# 7SEG-3.net
KiCad netlist of a schematic drawn in Altium Designer
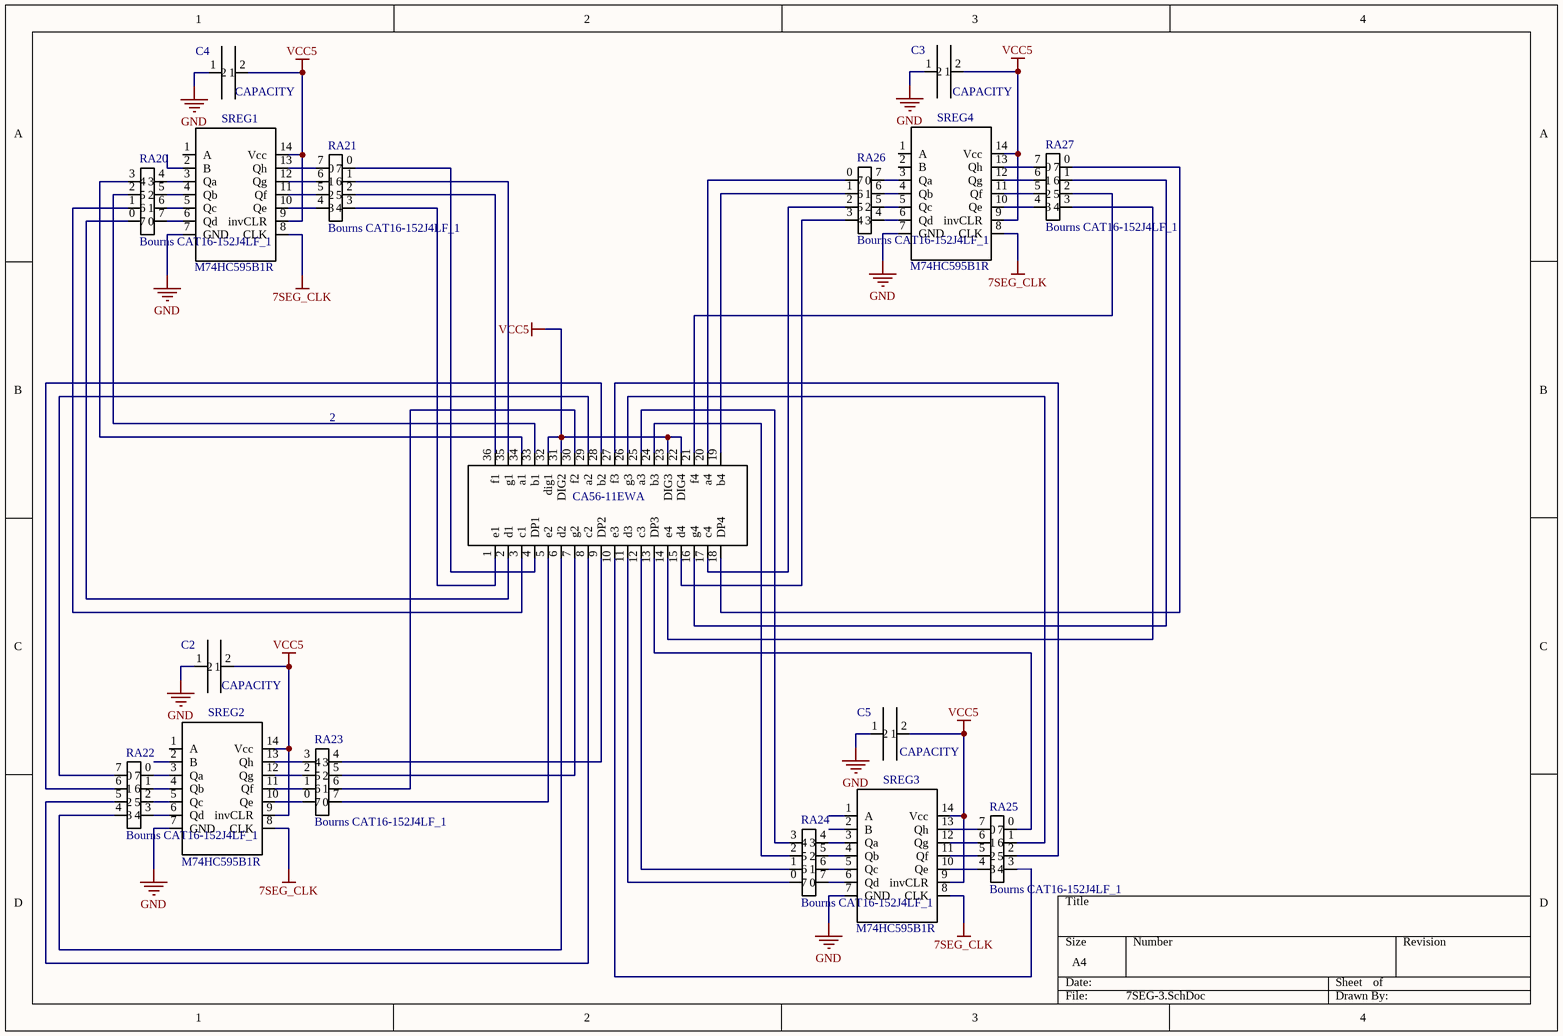
[diagram p0: 7SEG-3.SchDoc]

(export (version "E")
  (design (tool "Eeschema 10.0.6"))
  (components
    (comp (ref "2")
      (value "CA56-11EWA")
      (footprint "PcbLib1:CA56-11EWA")
      (libsource (lib "Library") (part "CA56-11EWA"))
    )
    (comp (ref "C2")
      (value "CAPACITY")
      (footprint "PcbLib1:R0805")
      (libsource (lib "Library") (part "CAPACITY"))
    )
    (comp (ref "C3")
      (value "CAPACITY")
      (footprint "PcbLib1:R0805")
      (libsource (lib "Library") (part "CAPACITY"))
    )
    (comp (ref "C4")
      (value "CAPACITY")
      (footprint "PcbLib1:R0805")
      (libsource (lib "Library") (part "CAPACITY"))
    )
    (comp (ref "C5")
      (value "CAPACITY")
      (footprint "PcbLib1:R0805")
      (libsource (lib "Library") (part "CAPACITY"))
    )
    (comp (ref "RA20")
      (value "Bourns CAT16-152J4LF_1")
      (footprint "PcbLib1:CAT16-102J4LF_2")
      (libsource (lib "Library") (part "Bourns CAT16-102J4LF_1"))
    )
    (comp (ref "RA21")
      (value "Bourns CAT16-152J4LF_1")
      (footprint "PcbLib1:CAT16-102J4LF_2")
      (libsource (lib "Library") (part "Bourns CAT16-102J4LF_1"))
    )
    (comp (ref "RA22")
      (value "Bourns CAT16-152J4LF_1")
      (footprint "PcbLib1:CAT16-102J4LF_2")
      (libsource (lib "Library") (part "Bourns CAT16-102J4LF_1"))
    )
    (comp (ref "RA23")
      (value "Bourns CAT16-152J4LF_1")
      (footprint "PcbLib1:CAT16-102J4LF_2")
      (libsource (lib "Library") (part "Bourns CAT16-102J4LF_1"))
    )
    (comp (ref "RA24")
      (value "Bourns CAT16-152J4LF_1")
      (footprint "PcbLib1:CAT16-102J4LF_2")
      (libsource (lib "Library") (part "Bourns CAT16-102J4LF_1"))
    )
    (comp (ref "RA25")
      (value "Bourns CAT16-152J4LF_1")
      (footprint "PcbLib1:CAT16-102J4LF_2")
      (libsource (lib "Library") (part "Bourns CAT16-102J4LF_1"))
    )
    (comp (ref "RA26")
      (value "Bourns CAT16-152J4LF_1")
      (footprint "PcbLib1:CAT16-102J4LF_2")
      (libsource (lib "Library") (part "Bourns CAT16-102J4LF_1"))
    )
    (comp (ref "RA27")
      (value "Bourns CAT16-152J4LF_1")
      (footprint "PcbLib1:CAT16-102J4LF_2")
      (libsource (lib "Library") (part "Bourns CAT16-102J4LF_1"))
    )
    (comp (ref "SREG1")
      (value "M74HC595B1R")
      (footprint "PcbLib1:SN74HC164DR-D")
      (libsource (lib "Library") (part "M74HC595B1R"))
    )
    (comp (ref "SREG2")
      (value "M74HC595B1R")
      (footprint "PcbLib1:SN74HC164DR-D")
      (libsource (lib "Library") (part "M74HC595B1R"))
    )
    (comp (ref "SREG3")
      (value "M74HC595B1R")
      (footprint "PcbLib1:SN74HC164DR-D")
      (libsource (lib "Library") (part "M74HC595B1R"))
    )
    (comp (ref "SREG4")
      (value "M74HC595B1R")
      (footprint "PcbLib1:SN74HC164DR-D")
      (libsource (lib "Library") (part "M74HC595B1R"))
    )
  )
  (nets
    (net (code "1") (name "7SEG_CLK") (class "Default")
      (node (ref "SREG1") (pin "8") (pinfunction "CLK_8") (pintype "passive"))
      (node (ref "SREG2") (pin "8") (pinfunction "CLK_8") (pintype "passive"))
      (node (ref "SREG3") (pin "8") (pinfunction "CLK_8") (pintype "passive"))
      (node (ref "SREG4") (pin "8") (pinfunction "CLK_8") (pintype "passive"))
    )
    (net (code "2") (name "GND") (class "Default")
      (node (ref "C2") (pin "1") (pinfunction "1_1") (pintype "passive"))
      (node (ref "C3") (pin "1") (pinfunction "1_1") (pintype "passive"))
      (node (ref "C4") (pin "1") (pinfunction "1_1") (pintype "passive"))
      (node (ref "C5") (pin "1") (pinfunction "1_1") (pintype "passive"))
      (node (ref "SREG1") (pin "7") (pinfunction "GND_7") (pintype "passive"))
      (node (ref "SREG2") (pin "7") (pinfunction "GND_7") (pintype "passive"))
      (node (ref "SREG3") (pin "7") (pinfunction "GND_7") (pintype "passive"))
      (node (ref "SREG4") (pin "7") (pinfunction "GND_7") (pintype "passive"))
    )
    (net (code "3") (name "Net-(2-DP1)") (class "Default")
      (node (ref "2") (pin "4") (pinfunction "DP1_4") (pintype "passive"))
      (node (ref "RA21") (pin "0") (pinfunction "0_0") (pintype "passive"))
    )
    (net (code "4") (name "Net-(2-DP2)") (class "Default")
      (node (ref "2") (pin "9") (pinfunction "DP2_9") (pintype "passive"))
      (node (ref "RA23") (pin "4") (pinfunction "4_4") (pintype "passive"))
    )
    (net (code "5") (name "Net-(2-DP3)") (class "Default")
      (node (ref "2") (pin "13") (pinfunction "DP3_13") (pintype "passive"))
      (node (ref "RA25") (pin "0") (pinfunction "0_0") (pintype "passive"))
    )
    (net (code "6") (name "Net-(2-DP4)") (class "Default")
      (node (ref "2") (pin "18") (pinfunction "DP4_18") (pintype "passive"))
      (node (ref "RA27") (pin "0") (pinfunction "0_0") (pintype "passive"))
    )
    (net (code "7") (name "Net-(2-a1)") (class "Default")
      (node (ref "2") (pin "34") (pinfunction "a1_34") (pintype "passive"))
      (node (ref "RA20") (pin "3") (pinfunction "3_3") (pintype "passive"))
    )
    (net (code "8") (name "Net-(2-a2)") (class "Default")
      (node (ref "2") (pin "29") (pinfunction "a2_29") (pintype "passive"))
      (node (ref "RA22") (pin "7") (pinfunction "7_7") (pintype "passive"))
    )
    (net (code "9") (name "Net-(2-a3)") (class "Default")
      (node (ref "2") (pin "25") (pinfunction "a3_25") (pintype "passive"))
      (node (ref "RA24") (pin "3") (pinfunction "3_3") (pintype "passive"))
    )
    (net (code "10") (name "Net-(2-a4)") (class "Default")
      (node (ref "2") (pin "20") (pinfunction "a4_20") (pintype "passive"))
      (node (ref "RA26") (pin "0") (pinfunction "0_0") (pintype "passive"))
    )
    (net (code "11") (name "Net-(2-b1)") (class "Default")
      (node (ref "2") (pin "33") (pinfunction "b1_33") (pintype "passive"))
      (node (ref "RA20") (pin "2") (pinfunction "2_2") (pintype "passive"))
    )
    (net (code "12") (name "Net-(2-b2)") (class "Default")
      (node (ref "2") (pin "28") (pinfunction "b2_28") (pintype "passive"))
      (node (ref "RA22") (pin "6") (pinfunction "6_6") (pintype "passive"))
    )
    (net (code "13") (name "Net-(2-b3)") (class "Default")
      (node (ref "2") (pin "24") (pinfunction "b3_24") (pintype "passive"))
      (node (ref "RA24") (pin "2") (pinfunction "2_2") (pintype "passive"))
    )
    (net (code "14") (name "Net-(2-b4)") (class "Default")
      (node (ref "2") (pin "19") (pinfunction "b4_19") (pintype "passive"))
      (node (ref "RA26") (pin "1") (pinfunction "1_1") (pintype "passive"))
    )
    (net (code "15") (name "Net-(2-c1)") (class "Default")
      (node (ref "2") (pin "3") (pinfunction "c1_3") (pintype "passive"))
      (node (ref "RA20") (pin "1") (pinfunction "1_1") (pintype "passive"))
    )
    (net (code "16") (name "Net-(2-c2)") (class "Default")
      (node (ref "2") (pin "8") (pinfunction "c2_8") (pintype "passive"))
      (node (ref "RA22") (pin "5") (pinfunction "5_5") (pintype "passive"))
    )
    (net (code "17") (name "Net-(2-c3)") (class "Default")
      (node (ref "2") (pin "12") (pinfunction "c3_12") (pintype "passive"))
      (node (ref "RA24") (pin "1") (pinfunction "1_1") (pintype "passive"))
    )
    (net (code "18") (name "Net-(2-c4)") (class "Default")
      (node (ref "2") (pin "17") (pinfunction "c4_17") (pintype "passive"))
      (node (ref "RA26") (pin "2") (pinfunction "2_2") (pintype "passive"))
    )
    (net (code "19") (name "Net-(2-d1)") (class "Default")
      (node (ref "2") (pin "2") (pinfunction "d1_2") (pintype "passive"))
      (node (ref "RA20") (pin "0") (pinfunction "0_0") (pintype "passive"))
    )
    (net (code "20") (name "Net-(2-d2)") (class "Default")
      (node (ref "2") (pin "6") (pinfunction "d2_6") (pintype "passive"))
      (node (ref "RA22") (pin "4") (pinfunction "4_4") (pintype "passive"))
    )
    (net (code "21") (name "Net-(2-d3)") (class "Default")
      (node (ref "2") (pin "11") (pinfunction "d3_11") (pintype "passive"))
      (node (ref "RA24") (pin "0") (pinfunction "0_0") (pintype "passive"))
    )
    (net (code "22") (name "Net-(2-d4)") (class "Default")
      (node (ref "2") (pin "15") (pinfunction "d4_15") (pintype "passive"))
      (node (ref "RA26") (pin "3") (pinfunction "3_3") (pintype "passive"))
    )
    (net (code "23") (name "Net-(2-e1)") (class "Default")
      (node (ref "2") (pin "1") (pinfunction "e1_1") (pintype "passive"))
      (node (ref "RA21") (pin "3") (pinfunction "3_3") (pintype "passive"))
    )
    (net (code "24") (name "Net-(2-e2)") (class "Default")
      (node (ref "2") (pin "5") (pinfunction "e2_5") (pintype "passive"))
      (node (ref "RA23") (pin "7") (pinfunction "7_7") (pintype "passive"))
    )
    (net (code "25") (name "Net-(2-e3)") (class "Default")
      (node (ref "2") (pin "10") (pinfunction "e3_10") (pintype "passive"))
      (node (ref "RA25") (pin "3") (pinfunction "3_3") (pintype "passive"))
    )
    (net (code "26") (name "Net-(2-e4)") (class "Default")
      (node (ref "2") (pin "14") (pinfunction "e4_14") (pintype "passive"))
      (node (ref "RA27") (pin "3") (pinfunction "3_3") (pintype "passive"))
    )
    (net (code "27") (name "Net-(2-f1)") (class "Default")
      (node (ref "2") (pin "36") (pinfunction "f1_36") (pintype "passive"))
      (node (ref "RA21") (pin "2") (pinfunction "2_2") (pintype "passive"))
    )
    (net (code "28") (name "Net-(2-f2)") (class "Default")
      (node (ref "2") (pin "30") (pinfunction "f2_30") (pintype "passive"))
      (node (ref "RA23") (pin "6") (pinfunction "6_6") (pintype "passive"))
    )
    (net (code "29") (name "Net-(2-f3)") (class "Default")
      (node (ref "2") (pin "27") (pinfunction "f3_27") (pintype "passive"))
      (node (ref "RA25") (pin "2") (pinfunction "2_2") (pintype "passive"))
    )
    (net (code "30") (name "Net-(2-f4)") (class "Default")
      (node (ref "2") (pin "21") (pinfunction "f4_21") (pintype "passive"))
      (node (ref "RA27") (pin "2") (pinfunction "2_2") (pintype "passive"))
    )
    (net (code "31") (name "Net-(2-g1)") (class "Default")
      (node (ref "2") (pin "35") (pinfunction "g1_35") (pintype "passive"))
      (node (ref "RA21") (pin "1") (pinfunction "1_1") (pintype "passive"))
    )
    (net (code "32") (name "Net-(2-g2)") (class "Default")
      (node (ref "2") (pin "7") (pinfunction "g2_7") (pintype "passive"))
      (node (ref "RA23") (pin "5") (pinfunction "5_5") (pintype "passive"))
    )
    (net (code "33") (name "Net-(2-g3)") (class "Default")
      (node (ref "2") (pin "26") (pinfunction "g3_26") (pintype "passive"))
      (node (ref "RA25") (pin "1") (pinfunction "1_1") (pintype "passive"))
    )
    (net (code "34") (name "Net-(2-g4)") (class "Default")
      (node (ref "2") (pin "16") (pinfunction "g4_16") (pintype "passive"))
      (node (ref "RA27") (pin "1") (pinfunction "1_1") (pintype "passive"))
    )
    (net (code "35") (name "Net-(SREG1-Qa)") (class "Default")
      (node (ref "RA20") (pin "4") (pinfunction "4_4") (pintype "passive"))
      (node (ref "SREG1") (pin "3") (pinfunction "Qa_3") (pintype "passive"))
    )
    (net (code "36") (name "Net-(SREG1-Qb)") (class "Default")
      (node (ref "RA20") (pin "5") (pinfunction "5_5") (pintype "passive"))
      (node (ref "SREG1") (pin "4") (pinfunction "Qb_4") (pintype "passive"))
    )
    (net (code "37") (name "Net-(SREG1-Qc)") (class "Default")
      (node (ref "RA20") (pin "6") (pinfunction "6_6") (pintype "passive"))
      (node (ref "SREG1") (pin "5") (pinfunction "Qc_5") (pintype "passive"))
    )
    (net (code "38") (name "Net-(SREG1-Qd)") (class "Default")
      (node (ref "RA20") (pin "7") (pinfunction "7_7") (pintype "passive"))
      (node (ref "SREG1") (pin "6") (pinfunction "Qd_6") (pintype "passive"))
    )
    (net (code "39") (name "Net-(SREG1-Qe)") (class "Default")
      (node (ref "RA21") (pin "4") (pinfunction "4_4") (pintype "passive"))
      (node (ref "SREG1") (pin "10") (pinfunction "Qe_10") (pintype "passive"))
    )
    (net (code "40") (name "Net-(SREG1-Qf)") (class "Default")
      (node (ref "RA21") (pin "5") (pinfunction "5_5") (pintype "passive"))
      (node (ref "SREG1") (pin "11") (pinfunction "Qf_11") (pintype "passive"))
    )
    (net (code "41") (name "Net-(SREG1-Qg)") (class "Default")
      (node (ref "RA21") (pin "6") (pinfunction "6_6") (pintype "passive"))
      (node (ref "SREG1") (pin "12") (pinfunction "Qg_12") (pintype "passive"))
    )
    (net (code "42") (name "Net-(SREG1-Qh)") (class "Default")
      (node (ref "RA21") (pin "7") (pinfunction "7_7") (pintype "passive"))
      (node (ref "SREG1") (pin "13") (pinfunction "Qh_13") (pintype "passive"))
    )
    (net (code "43") (name "Net-(SREG2-Qa)") (class "Default")
      (node (ref "RA22") (pin "0") (pinfunction "0_0") (pintype "passive"))
      (node (ref "SREG2") (pin "3") (pinfunction "Qa_3") (pintype "passive"))
    )
    (net (code "44") (name "Net-(SREG2-Qb)") (class "Default")
      (node (ref "RA22") (pin "1") (pinfunction "1_1") (pintype "passive"))
      (node (ref "SREG2") (pin "4") (pinfunction "Qb_4") (pintype "passive"))
    )
    (net (code "45") (name "Net-(SREG2-Qc)") (class "Default")
      (node (ref "RA22") (pin "2") (pinfunction "2_2") (pintype "passive"))
      (node (ref "SREG2") (pin "5") (pinfunction "Qc_5") (pintype "passive"))
    )
    (net (code "46") (name "Net-(SREG2-Qd)") (class "Default")
      (node (ref "RA22") (pin "3") (pinfunction "3_3") (pintype "passive"))
      (node (ref "SREG2") (pin "6") (pinfunction "Qd_6") (pintype "passive"))
    )
    (net (code "47") (name "Net-(SREG2-Qe)") (class "Default")
      (node (ref "RA23") (pin "0") (pinfunction "0_0") (pintype "passive"))
      (node (ref "SREG2") (pin "10") (pinfunction "Qe_10") (pintype "passive"))
    )
    (net (code "48") (name "Net-(SREG2-Qf)") (class "Default")
      (node (ref "RA23") (pin "1") (pinfunction "1_1") (pintype "passive"))
      (node (ref "SREG2") (pin "11") (pinfunction "Qf_11") (pintype "passive"))
    )
    (net (code "49") (name "Net-(SREG2-Qg)") (class "Default")
      (node (ref "RA23") (pin "2") (pinfunction "2_2") (pintype "passive"))
      (node (ref "SREG2") (pin "12") (pinfunction "Qg_12") (pintype "passive"))
    )
    (net (code "50") (name "Net-(SREG2-Qh)") (class "Default")
      (node (ref "RA23") (pin "3") (pinfunction "3_3") (pintype "passive"))
      (node (ref "SREG2") (pin "13") (pinfunction "Qh_13") (pintype "passive"))
    )
    (net (code "51") (name "Net-(SREG3-Qa)") (class "Default")
      (node (ref "RA24") (pin "4") (pinfunction "4_4") (pintype "passive"))
      (node (ref "SREG3") (pin "3") (pinfunction "Qa_3") (pintype "passive"))
    )
    (net (code "52") (name "Net-(SREG3-Qb)") (class "Default")
      (node (ref "RA24") (pin "5") (pinfunction "5_5") (pintype "passive"))
      (node (ref "SREG3") (pin "4") (pinfunction "Qb_4") (pintype "passive"))
    )
    (net (code "53") (name "Net-(SREG3-Qc)") (class "Default")
      (node (ref "RA24") (pin "6") (pinfunction "6_6") (pintype "passive"))
      (node (ref "SREG3") (pin "5") (pinfunction "Qc_5") (pintype "passive"))
    )
    (net (code "54") (name "Net-(SREG3-Qd)") (class "Default")
      (node (ref "RA24") (pin "7") (pinfunction "7_7") (pintype "passive"))
      (node (ref "SREG3") (pin "6") (pinfunction "Qd_6") (pintype "passive"))
    )
    (net (code "55") (name "Net-(SREG3-Qe)") (class "Default")
      (node (ref "RA25") (pin "4") (pinfunction "4_4") (pintype "passive"))
      (node (ref "SREG3") (pin "10") (pinfunction "Qe_10") (pintype "passive"))
    )
    (net (code "56") (name "Net-(SREG3-Qf)") (class "Default")
      (node (ref "RA25") (pin "5") (pinfunction "5_5") (pintype "passive"))
      (node (ref "SREG3") (pin "11") (pinfunction "Qf_11") (pintype "passive"))
    )
    (net (code "57") (name "Net-(SREG3-Qg)") (class "Default")
      (node (ref "RA25") (pin "6") (pinfunction "6_6") (pintype "passive"))
      (node (ref "SREG3") (pin "12") (pinfunction "Qg_12") (pintype "passive"))
    )
    (net (code "58") (name "Net-(SREG3-Qh)") (class "Default")
      (node (ref "RA25") (pin "7") (pinfunction "7_7") (pintype "passive"))
      (node (ref "SREG3") (pin "13") (pinfunction "Qh_13") (pintype "passive"))
    )
    (net (code "59") (name "Net-(SREG4-Qa)") (class "Default")
      (node (ref "RA26") (pin "7") (pinfunction "7_7") (pintype "passive"))
      (node (ref "SREG4") (pin "3") (pinfunction "Qa_3") (pintype "passive"))
    )
    (net (code "60") (name "Net-(SREG4-Qb)") (class "Default")
      (node (ref "RA26") (pin "6") (pinfunction "6_6") (pintype "passive"))
      (node (ref "SREG4") (pin "4") (pinfunction "Qb_4") (pintype "passive"))
    )
    (net (code "61") (name "Net-(SREG4-Qc)") (class "Default")
      (node (ref "RA26") (pin "5") (pinfunction "5_5") (pintype "passive"))
      (node (ref "SREG4") (pin "5") (pinfunction "Qc_5") (pintype "passive"))
    )
    (net (code "62") (name "Net-(SREG4-Qd)") (class "Default")
      (node (ref "RA26") (pin "4") (pinfunction "4_4") (pintype "passive"))
      (node (ref "SREG4") (pin "6") (pinfunction "Qd_6") (pintype "passive"))
    )
    (net (code "63") (name "Net-(SREG4-Qe)") (class "Default")
      (node (ref "RA27") (pin "4") (pinfunction "4_4") (pintype "passive"))
      (node (ref "SREG4") (pin "10") (pinfunction "Qe_10") (pintype "passive"))
    )
    (net (code "64") (name "Net-(SREG4-Qf)") (class "Default")
      (node (ref "RA27") (pin "5") (pinfunction "5_5") (pintype "passive"))
      (node (ref "SREG4") (pin "11") (pinfunction "Qf_11") (pintype "passive"))
    )
    (net (code "65") (name "Net-(SREG4-Qg)") (class "Default")
      (node (ref "RA27") (pin "6") (pinfunction "6_6") (pintype "passive"))
      (node (ref "SREG4") (pin "12") (pinfunction "Qg_12") (pintype "passive"))
    )
    (net (code "66") (name "Net-(SREG4-Qh)") (class "Default")
      (node (ref "RA27") (pin "7") (pinfunction "7_7") (pintype "passive"))
      (node (ref "SREG4") (pin "13") (pinfunction "Qh_13") (pintype "passive"))
    )
    (net (code "67") (name "VCC5") (class "Default")
      (node (ref "2") (pin "22") (pinfunction "DIG4_22") (pintype "passive"))
      (node (ref "2") (pin "23") (pinfunction "DIG3_23") (pintype "passive"))
      (node (ref "2") (pin "31") (pinfunction "DIG2_31") (pintype "passive"))
      (node (ref "2") (pin "32") (pinfunction "dig1_32") (pintype "passive"))
      (node (ref "C2") (pin "2") (pinfunction "2_2") (pintype "passive"))
      (node (ref "C3") (pin "2") (pinfunction "2_2") (pintype "passive"))
      (node (ref "C4") (pin "2") (pinfunction "2_2") (pintype "passive"))
      (node (ref "C5") (pin "2") (pinfunction "2_2") (pintype "passive"))
      (node (ref "SREG1") (pin "14") (pinfunction "Vcc_14") (pintype "passive"))
      (node (ref "SREG1") (pin "9") (pinfunction "invCLR_9") (pintype "passive"))
      (node (ref "SREG2") (pin "14") (pinfunction "Vcc_14") (pintype "passive"))
      (node (ref "SREG2") (pin "9") (pinfunction "invCLR_9") (pintype "passive"))
      (node (ref "SREG3") (pin "14") (pinfunction "Vcc_14") (pintype "passive"))
      (node (ref "SREG3") (pin "9") (pinfunction "invCLR_9") (pintype "passive"))
      (node (ref "SREG4") (pin "14") (pinfunction "Vcc_14") (pintype "passive"))
      (node (ref "SREG4") (pin "9") (pinfunction "invCLR_9") (pintype "passive"))
    )
    (net (code "68") (name "unconnected-(SREG1-A-Pad1)") (class "Default")
      (node (ref "SREG1") (pin "1") (pinfunction "A_1") (pintype "passive"))
    )
    (net (code "69") (name "unconnected-(SREG1-B-Pad2)") (class "Default")
      (node (ref "SREG1") (pin "2") (pinfunction "B_2") (pintype "passive"))
    )
    (net (code "70") (name "unconnected-(SREG2-A-Pad1)") (class "Default")
      (node (ref "SREG2") (pin "1") (pinfunction "A_1") (pintype "passive"))
    )
    (net (code "71") (name "unconnected-(SREG2-B-Pad2)") (class "Default")
      (node (ref "SREG2") (pin "2") (pinfunction "B_2") (pintype "passive"))
    )
    (net (code "72") (name "unconnected-(SREG3-A-Pad1)") (class "Default")
      (node (ref "SREG3") (pin "1") (pinfunction "A_1") (pintype "passive"))
    )
    (net (code "73") (name "unconnected-(SREG3-B-Pad2)") (class "Default")
      (node (ref "SREG3") (pin "2") (pinfunction "B_2") (pintype "passive"))
    )
    (net (code "74") (name "unconnected-(SREG4-A-Pad1)") (class "Default")
      (node (ref "SREG4") (pin "1") (pinfunction "A_1") (pintype "passive"))
    )
    (net (code "75") (name "unconnected-(SREG4-B-Pad2)") (class "Default")
      (node (ref "SREG4") (pin "2") (pinfunction "B_2") (pintype "passive"))
    )
  )
)
